# JN5169.net
KiCad netlist of a schematic drawn in Altium Designer
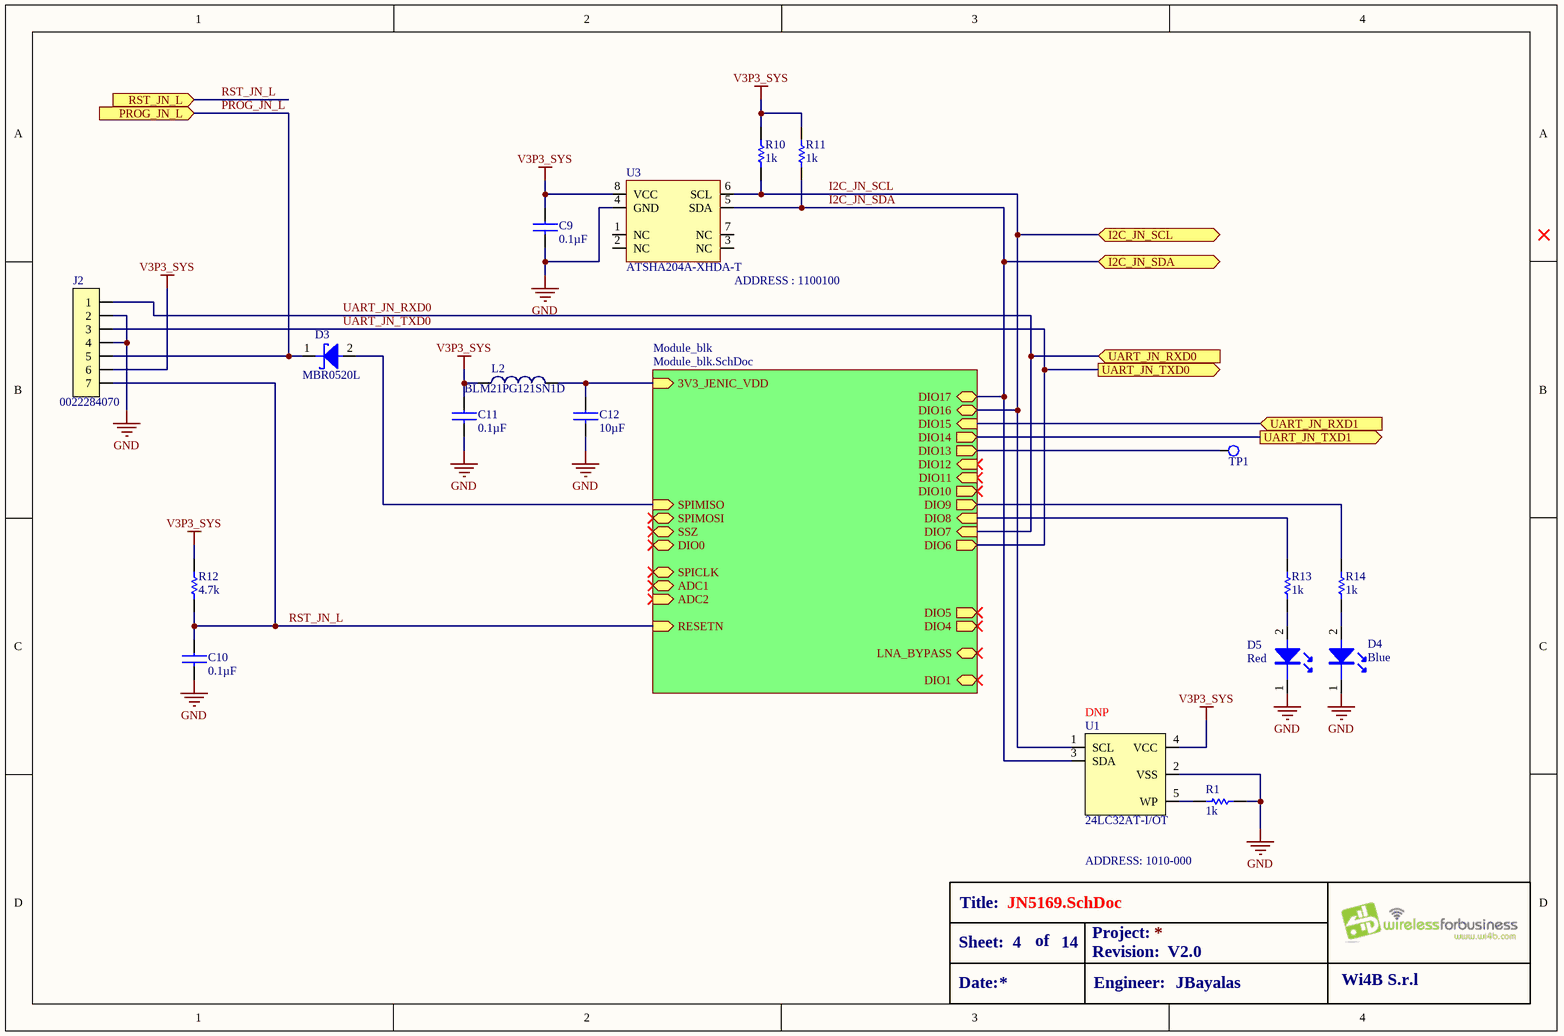
[diagram p0: JN5169.SchDoc]

(export (version "E")
  (design (tool "Eeschema 10.0.6"))
  (components
    (comp (ref "C9")
      (value "0.1µF")
      (footprint "C0402")
      (description "CAP CER 0.1UF 16V X7R 0402")
      (fields (field (name "MPN") "CL05B104KO3LNNC"))
      (libsource (lib "Capacitor") (part "CL05B104KO3LNNC"))
    )
    (comp (ref "C10")
      (value "0.1µF")
      (footprint "C0402")
      (description "CAP CER 0.1UF 16V X7R 0402")
      (fields (field (name "MPN") "CL05B104KO3LNNC"))
      (libsource (lib "Capacitor") (part "CL05B104KO3LNNC"))
    )
    (comp (ref "C11")
      (value "0.1µF")
      (footprint "C0402")
      (description "CAP CER 0.1UF 16V X7R 0402")
      (fields (field (name "MPN") "CL05B104KO3LNNC"))
      (libsource (lib "Capacitor") (part "CL05B104KO3LNNC"))
    )
    (comp (ref "C12")
      (value "10µF")
      (footprint "C0805")
      (description "CAP CER 10UF 6.3V X5R 0805")
      (fields (field (name "MPN") "GRM219R60J106KE19D"))
      (libsource (lib "Capacitor") (part "GRM219R60J106KE19D"))
    )
    (comp (ref "D3")
      (value "MBR0520L")
      (footprint "SOD123")
      (description "DIODE SCHOTTKY 20V 0.5A SOD123")
      (fields (field (name "MPN") "MBR0520L"))
      (libsource (lib "Diode") (part "MBR0520L"))
    )
    (comp (ref "D4")
      (value "Blue")
      (footprint "LED-0603 (BLUE)")
      (description "LED BLUE CLEAR 0603 SMD")
      (fields (field (name "MPN") "LTST-C191TBKT"))
      (libsource (lib "Diode") (part "LTST-C191TBKT"))
    )
    (comp (ref "D5")
      (value "Red")
      (footprint "LED0805 - (RED)")
      (description "LED CHIPLED 633NM RED 0805 SMD")
      (fields (field (name "MPN") "LS R976-NR-1"))
      (libsource (lib "Diode") (part "LS R976-NR-1"))
    )
    (comp (ref "J2")
      (value "*")
      (footprint "0022284070")
      (description "CONN HEADER 7POS .100 VERT TIN")
      (fields (field (name "MPN") "0022284070"))
      (libsource (lib "Connector") (part "0022284070"))
    )
    (comp (ref "L2")
      (value "*")
      (footprint "0805 INDUCTOR")
      (description "FERRITE CHIP 120 OHM 0805")
      (fields (field (name "MPN") "BLM21PG121SN1D"))
      (libsource (lib "Inductor") (part "BLM21PG121SN1D"))
    )
    (comp (ref "R1")
      (value "1k")
      (footprint "R0402")
      (description "RES SMD 1K OHM 1% 1/10W 0402")
      (fields (field (name "MPN") "MCS04020C1001FE000"))
      (libsource (lib "Res") (part "MCS04020C1001FE000"))
    )
    (comp (ref "R10")
      (value "1k")
      (footprint "R0402")
      (description "RES SMD 1K OHM 1% 1/10W 0402")
      (fields (field (name "MPN") "MCS04020C1001FE000"))
      (libsource (lib "Res") (part "MCS04020C1001FE000"))
    )
    (comp (ref "R11")
      (value "1k")
      (footprint "R0402")
      (description "RES SMD 1K OHM 1% 1/10W 0402")
      (fields (field (name "MPN") "MCS04020C1001FE000"))
      (libsource (lib "Res") (part "MCS04020C1001FE000"))
    )
    (comp (ref "R12")
      (value "4.7k")
      (footprint "R0603")
      (description "RES SMD 4.7K OHM 0.1% 1/10W 0603")
      (fields (field (name "MPN") "ERA-3AEB472V"))
      (libsource (lib "Res") (part "ERA-3AEB472V"))
    )
    (comp (ref "R13")
      (value "1k")
      (footprint "R0603")
      (description "RES SMD 1K OHM 1% 1/10W 0603")
      (fields (field (name "MPN") "ERJ-3EKF1001V"))
      (libsource (lib "Res") (part "ERJ-3EKF1001V"))
    )
    (comp (ref "R14")
      (value "1k")
      (footprint "R0603")
      (description "RES SMD 1K OHM 1% 1/10W 0603")
      (fields (field (name "MPN") "ERJ-3EKF1001V"))
      (libsource (lib "Res") (part "ERJ-3EKF1001V"))
    )
    (comp (ref "TP1")
      (value "*")
      (footprint "Test Point 1.27mm")
      (description "Test Point 1.27mm")
      (libsource (lib "Miscellaneous") (part "Test Point"))
    )
    (comp (ref "U1")
      (value "*")
      (footprint "SOT-23-5")
      (description "IC EEPROM 32KBIT 400KHZ SOT23-5")
      (fields (field (name "LOAD") "DNP") (field (name "MPN") "24LC32AT-I/OT"))
      (libsource (lib "IC") (part "24LC32AT-I/OT"))
    )
    (comp (ref "U3")
      (value "ATSHA204A-XHDA-T")
      (footprint "TSSOP-8 (wide Body)")
      (description "IC CRYPTO 4.5KB I2C")
      (fields (field (name "MPN") "ATSHA204A-XHDA-T"))
      (libsource (lib "IC") (part "ATSHA204A-XHDA-T"))
    )
  )
  (nets
    (net (code "1") (name "/3V3_JENIC_VDD") (class "Default")
      (node (ref "C12") (pin "1") (pinfunction "1_1") (pintype "passive"))
      (node (ref "L2") (pin "1") (pinfunction "1_1") (pintype "passive"))
    )
    (net (code "8") (name "/DIO8") (class "Default")
      (node (ref "R13") (pin "1") (pinfunction "1_1") (pintype "passive"))
    )
    (net (code "9") (name "/DIO9") (class "Default")
      (node (ref "R14") (pin "1") (pinfunction "1_1") (pintype "passive"))
    )
    (net (code "13") (name "/DIO13") (class "Default")
      (node (ref "TP1") (pin "1") (pinfunction "1_1") (pintype "passive"))
    )
    (net (code "14") (name "/I2C_JN_SCL") (class "Default")
      (node (ref "R10") (pin "1") (pinfunction "1_1") (pintype "passive"))
      (node (ref "U1") (pin "1") (pinfunction "SCL_1") (pintype "passive"))
      (node (ref "U3") (pin "6") (pinfunction "SCL_6") (pintype "passive"))
    )
    (net (code "15") (name "/I2C_JN_SDA") (class "Default")
      (node (ref "R11") (pin "1") (pinfunction "1_1") (pintype "passive"))
      (node (ref "U1") (pin "3") (pinfunction "SDA_3") (pintype "passive"))
      (node (ref "U3") (pin "5") (pinfunction "SDA_5") (pintype "passive"))
    )
    (net (code "17") (name "/PROG_JN_L") (class "Default")
      (node (ref "D3") (pin "1") (pinfunction "cathode_1") (pintype "passive"))
      (node (ref "J2") (pin "5") (pinfunction "5_5") (pintype "passive"))
    )
    (net (code "18") (name "/RST_JN_L") (class "Default")
      (node (ref "C10") (pin "1") (pinfunction "1_1") (pintype "passive"))
      (node (ref "J2") (pin "7") (pinfunction "7_7") (pintype "passive"))
      (node (ref "R12") (pin "1") (pinfunction "1_1") (pintype "passive"))
    )
    (net (code "20") (name "/SPIMISO") (class "Default")
      (node (ref "D3") (pin "2") (pinfunction "anode_2") (pintype "passive"))
    )
    (net (code "23") (name "/UART_JN_RXD0") (class "Default")
      (node (ref "J2") (pin "1") (pinfunction "1_1") (pintype "passive"))
    )
    (net (code "25") (name "/UART_JN_TXD0") (class "Default")
      (node (ref "J2") (pin "3") (pinfunction "3_3") (pintype "passive"))
    )
    (net (code "27") (name "GND") (class "Default")
      (node (ref "C10") (pin "2") (pinfunction "2_2") (pintype "passive"))
      (node (ref "C11") (pin "2") (pinfunction "2_2") (pintype "passive"))
      (node (ref "C12") (pin "2") (pinfunction "2_2") (pintype "passive"))
      (node (ref "C9") (pin "2") (pinfunction "2_2") (pintype "passive"))
      (node (ref "D4") (pin "1") (pinfunction "1_1") (pintype "passive"))
      (node (ref "D5") (pin "1") (pinfunction "1_1") (pintype "passive"))
      (node (ref "J2") (pin "2") (pinfunction "2_2") (pintype "passive"))
      (node (ref "J2") (pin "4") (pinfunction "4_4") (pintype "passive"))
      (node (ref "R1") (pin "2") (pinfunction "2_2") (pintype "passive"))
      (node (ref "U1") (pin "2") (pinfunction "VSS_2") (pintype "passive"))
      (node (ref "U3") (pin "4") (pinfunction "GND_4") (pintype "passive"))
    )
    (net (code "28") (name "Net-(D4-Pad2)") (class "Default")
      (node (ref "D4") (pin "2") (pinfunction "2_2") (pintype "passive"))
      (node (ref "R14") (pin "2") (pinfunction "2_2") (pintype "passive"))
    )
    (net (code "29") (name "Net-(D5-Pad2)") (class "Default")
      (node (ref "D5") (pin "2") (pinfunction "2_2") (pintype "passive"))
      (node (ref "R13") (pin "2") (pinfunction "2_2") (pintype "passive"))
    )
    (net (code "30") (name "Net-(U1-WP)") (class "Default")
      (node (ref "R1") (pin "1") (pinfunction "1_1") (pintype "passive"))
      (node (ref "U1") (pin "5") (pinfunction "WP_5") (pintype "passive"))
    )
    (net (code "31") (name "V3P3_SYS") (class "Default")
      (node (ref "C11") (pin "1") (pinfunction "1_1") (pintype "passive"))
      (node (ref "C9") (pin "1") (pinfunction "1_1") (pintype "passive"))
      (node (ref "J2") (pin "6") (pinfunction "6_6") (pintype "passive"))
      (node (ref "L2") (pin "2") (pinfunction "2_2") (pintype "passive"))
      (node (ref "R10") (pin "2") (pinfunction "2_2") (pintype "passive"))
      (node (ref "R11") (pin "2") (pinfunction "2_2") (pintype "passive"))
      (node (ref "R12") (pin "2") (pinfunction "2_2") (pintype "passive"))
      (node (ref "U1") (pin "4") (pinfunction "VCC_4") (pintype "passive"))
      (node (ref "U3") (pin "8") (pinfunction "VCC_8") (pintype "passive"))
    )
    (net (code "32") (name "unconnected-(U3-NC-Pad1)") (class "Default")
      (node (ref "U3") (pin "1") (pinfunction "NC_1") (pintype "passive"))
    )
    (net (code "33") (name "unconnected-(U3-NC-Pad2)") (class "Default")
      (node (ref "U3") (pin "2") (pinfunction "NC_2") (pintype "passive"))
    )
    (net (code "34") (name "unconnected-(U3-NC-Pad3)") (class "Default")
      (node (ref "U3") (pin "3") (pinfunction "NC_3") (pintype "passive"))
    )
    (net (code "35") (name "unconnected-(U3-NC-Pad7)") (class "Default")
      (node (ref "U3") (pin "7") (pinfunction "NC_7") (pintype "passive"))
    )
  )
)
